# cpld.net
KiCad netlist of a schematic drawn in Altium Designer
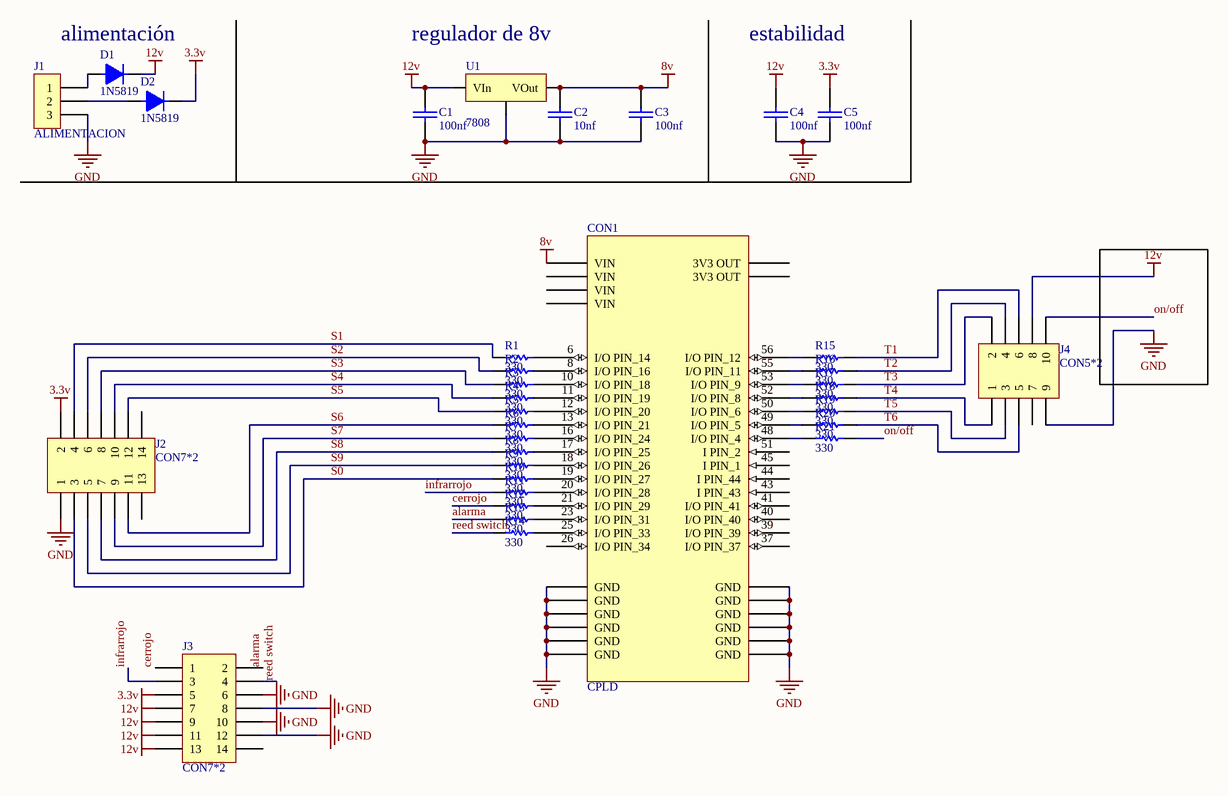
[diagram p0: cpld.SchDoc]

(export (version "E")
  (design (tool "Eeschema 10.0.6"))
  (components
    (comp (ref "C1") (value "100nf") (footprint "CAP200") (libsource (lib "LIBPIOIX") (part "CAP")))
    (comp (ref "C2") (value "10nf") (footprint "CAP200") (libsource (lib "LIBPIOIX") (part "CAP")))
    (comp (ref "C3") (value "100nf") (footprint "CAP200") (libsource (lib "LIBPIOIX") (part "CAP")))
    (comp (ref "C4") (value "100nf") (footprint "CAP200") (libsource (lib "LIBEBAL") (part "CAP")))
    (comp (ref "C5") (value "100nf") (footprint "CAP200") (libsource (lib "LIBEBAL") (part "CAP")))
    (comp (ref "CON1")
      (value "CPLD")
      (footprint "CPLD_CON")
      (description "Conector para Placa PIO CPLD")
      (fields (field (name "AUTOR") "AP"))
      (libsource (lib "CPLD_CON") (part "CPLD_CON"))
    )
    (comp (ref "D1") (value "1N5819") (footprint "DO41") (libsource (lib "LIBPIOIX") (part "DIODO")))
    (comp (ref "D2") (value "1N5819") (footprint "DO41") (libsource (lib "Libreria4") (part "DIODO")))
    (comp (ref "J1")
      (value "ALIMENTACION")
      (footprint "BORNERA3")
      (libsource (lib "Libreria4") (part "BORNERA 3"))
    )
    (comp (ref "J2") (value "CON7*2") (footprint "SIP7*2") (libsource (lib "LIBEBAL") (part "CON7*2")))
    (comp (ref "J3") (value "CON7*2") (footprint "SIP7*2") (libsource (lib "") (part "CON7*2_1")))
    (comp (ref "J4") (value "CON5*2") (footprint "SIP5*2") (libsource (lib "Libreria4") (part "CON5*2")))
    (comp (ref "R1") (value "330") (footprint "RES400") (libsource (lib "LIBPIOIX") (part "RES")))
    (comp (ref "R2") (value "330") (footprint "RES400") (libsource (lib "LIBPIOIX") (part "RES")))
    (comp (ref "R3") (value "330") (footprint "RES400") (libsource (lib "LIBPIOIX") (part "RES")))
    (comp (ref "R4") (value "330") (footprint "RES400") (libsource (lib "LIBPIOIX") (part "RES")))
    (comp (ref "R5") (value "330") (footprint "RES400") (libsource (lib "LIBPIOIX") (part "RES")))
    (comp (ref "R6") (value "330") (footprint "RES400") (libsource (lib "LIBPIOIX") (part "RES")))
    (comp (ref "R7") (value "330") (footprint "RES400") (libsource (lib "LIBPIOIX") (part "RES")))
    (comp (ref "R8") (value "330") (footprint "RES400") (libsource (lib "LIBPIOIX") (part "RES")))
    (comp (ref "R9") (value "330") (footprint "RES400") (libsource (lib "LIBPIOIX") (part "RES")))
    (comp (ref "R10") (value "330") (footprint "RES400") (libsource (lib "LIBPIOIX") (part "RES")))
    (comp (ref "R11") (value "330") (footprint "RES400") (libsource (lib "LIBPIOIX") (part "RES")))
    (comp (ref "R12") (value "330") (footprint "RES400") (libsource (lib "LIBPIOIX") (part "RES")))
    (comp (ref "R13") (value "330") (footprint "RES400") (libsource (lib "LIBPIOIX") (part "RES")))
    (comp (ref "R14") (value "330") (footprint "RES400") (libsource (lib "LIBPIOIX") (part "RES")))
    (comp (ref "R15") (value "330") (footprint "RES400") (libsource (lib "LIBPIOIX") (part "RES")))
    (comp (ref "R16") (value "330") (footprint "RES400") (libsource (lib "LIBPIOIX") (part "RES")))
    (comp (ref "R17") (value "330") (footprint "RES400") (libsource (lib "LIBPIOIX") (part "RES")))
    (comp (ref "R18") (value "330") (footprint "RES400") (libsource (lib "LIBPIOIX") (part "RES")))
    (comp (ref "R19") (value "330") (footprint "RES400") (libsource (lib "LIBPIOIX") (part "RES")))
    (comp (ref "R20") (value "330") (footprint "RES400") (libsource (lib "LIBPIOIX") (part "RES")))
    (comp (ref "R21") (value "330") (footprint "RES400") (libsource (lib "LIBPIOIX") (part "RES")))
    (comp (ref "U1")
      (value "7808")
      (footprint "TO-220 V")
      (description "REGULDOR POSITIVO")
      (libsource (lib "LIBPIOIX") (part "78XX"))
    )
  )
  (nets
    (net (code "1") (name "/S0") (class "Default")
      (node (ref "J2") (pin "3") (pinfunction "3_3") (pintype "passive"))
      (node (ref "R10") (pin "1") (pinfunction "1_1") (pintype "passive"))
    )
    (net (code "2") (name "/S1") (class "Default")
      (node (ref "J2") (pin "4") (pinfunction "4_4") (pintype "passive"))
      (node (ref "R1") (pin "1") (pinfunction "1_1") (pintype "passive"))
    )
    (net (code "3") (name "/S2") (class "Default")
      (node (ref "J2") (pin "6") (pinfunction "6_6") (pintype "passive"))
      (node (ref "R2") (pin "1") (pinfunction "1_1") (pintype "passive"))
    )
    (net (code "4") (name "/S3") (class "Default")
      (node (ref "J2") (pin "8") (pinfunction "8_8") (pintype "passive"))
      (node (ref "R3") (pin "1") (pinfunction "1_1") (pintype "passive"))
    )
    (net (code "5") (name "/S4") (class "Default")
      (node (ref "J2") (pin "10") (pinfunction "10_10") (pintype "passive"))
      (node (ref "R4") (pin "1") (pinfunction "1_1") (pintype "passive"))
    )
    (net (code "6") (name "/S5") (class "Default")
      (node (ref "J2") (pin "12") (pinfunction "12_12") (pintype "passive"))
      (node (ref "R5") (pin "1") (pinfunction "1_1") (pintype "passive"))
    )
    (net (code "7") (name "/S6") (class "Default")
      (node (ref "J2") (pin "11") (pinfunction "11_11") (pintype "passive"))
      (node (ref "R6") (pin "1") (pinfunction "1_1") (pintype "passive"))
    )
    (net (code "8") (name "/S7") (class "Default")
      (node (ref "J2") (pin "9") (pinfunction "9_9") (pintype "passive"))
      (node (ref "R7") (pin "1") (pinfunction "1_1") (pintype "passive"))
    )
    (net (code "9") (name "/S8") (class "Default")
      (node (ref "J2") (pin "7") (pinfunction "7_7") (pintype "passive"))
      (node (ref "R8") (pin "1") (pinfunction "1_1") (pintype "passive"))
    )
    (net (code "10") (name "/S9") (class "Default")
      (node (ref "J2") (pin "5") (pinfunction "5_5") (pintype "passive"))
      (node (ref "R9") (pin "1") (pinfunction "1_1") (pintype "passive"))
    )
    (net (code "11") (name "/T1") (class "Default")
      (node (ref "J4") (pin "6") (pinfunction "6_6") (pintype "passive"))
      (node (ref "R15") (pin "2") (pinfunction "2_2") (pintype "passive"))
    )
    (net (code "12") (name "/T2") (class "Default")
      (node (ref "J4") (pin "4") (pinfunction "4_4") (pintype "passive"))
      (node (ref "R16") (pin "2") (pinfunction "2_2") (pintype "passive"))
    )
    (net (code "13") (name "/T3") (class "Default")
      (node (ref "J4") (pin "2") (pinfunction "2_2") (pintype "passive"))
      (node (ref "R17") (pin "2") (pinfunction "2_2") (pintype "passive"))
    )
    (net (code "14") (name "/T4") (class "Default")
      (node (ref "J4") (pin "1") (pinfunction "1_1") (pintype "passive"))
      (node (ref "R18") (pin "2") (pinfunction "2_2") (pintype "passive"))
    )
    (net (code "15") (name "/T5") (class "Default")
      (node (ref "J4") (pin "3") (pinfunction "3_3") (pintype "passive"))
      (node (ref "R19") (pin "2") (pinfunction "2_2") (pintype "passive"))
    )
    (net (code "16") (name "/T6") (class "Default")
      (node (ref "J4") (pin "5") (pinfunction "5_5") (pintype "passive"))
      (node (ref "R20") (pin "2") (pinfunction "2_2") (pintype "passive"))
    )
    (net (code "17") (name "/alarma") (class "Default")
      (node (ref "J3") (pin "2") (pinfunction "2_2") (pintype "passive"))
      (node (ref "R13") (pin "1") (pinfunction "1_1") (pintype "passive"))
    )
    (net (code "18") (name "/cerrojo") (class "Default")
      (node (ref "J3") (pin "1") (pinfunction "1_1") (pintype "passive"))
      (node (ref "R12") (pin "1") (pinfunction "1_1") (pintype "passive"))
    )
    (net (code "19") (name "/infrarrojo") (class "Default")
      (node (ref "J3") (pin "3") (pinfunction "3_3") (pintype "passive"))
      (node (ref "R11") (pin "1") (pinfunction "1_1") (pintype "passive"))
    )
    (net (code "20") (name "/on{slash}off") (class "Default")
      (node (ref "J4") (pin "10") (pinfunction "10_10") (pintype "passive"))
      (node (ref "R21") (pin "2") (pinfunction "2_2") (pintype "passive"))
    )
    (net (code "21") (name "/reed switch") (class "Default")
      (node (ref "J3") (pin "4") (pinfunction "4_4") (pintype "passive"))
      (node (ref "R14") (pin "1") (pinfunction "1_1") (pintype "passive"))
    )
    (net (code "22") (name "3.3v") (class "Default")
      (node (ref "C5") (pin "1") (pinfunction "1_1") (pintype "passive"))
      (node (ref "D2") (pin "2") (pinfunction "2_2") (pintype "passive"))
      (node (ref "J2") (pin "2") (pinfunction "2_2") (pintype "passive"))
      (node (ref "J3") (pin "5") (pinfunction "5_5") (pintype "passive"))
    )
    (net (code "23") (name "8v") (class "Default")
      (node (ref "C2") (pin "1") (pinfunction "1_1") (pintype "passive"))
      (node (ref "C3") (pin "1") (pinfunction "1_1") (pintype "passive"))
      (node (ref "CON1") (pin "1") (pinfunction "VIN_1") (pintype "passive"))
      (node (ref "U1") (pin "3") (pinfunction "VOut_3") (pintype "passive"))
    )
    (net (code "24") (name "12v") (class "Default")
      (node (ref "C1") (pin "1") (pinfunction "1_1") (pintype "passive"))
      (node (ref "C4") (pin "1") (pinfunction "1_1") (pintype "passive"))
      (node (ref "D1") (pin "2") (pinfunction "2_2") (pintype "passive"))
      (node (ref "J3") (pin "11") (pinfunction "11_11") (pintype "passive"))
      (node (ref "J3") (pin "13") (pinfunction "13_13") (pintype "passive"))
      (node (ref "J3") (pin "7") (pinfunction "7_7") (pintype "passive"))
      (node (ref "J3") (pin "9") (pinfunction "9_9") (pintype "passive"))
      (node (ref "J4") (pin "8") (pinfunction "8_8") (pintype "passive"))
      (node (ref "U1") (pin "1") (pinfunction "VIn_1") (pintype "passive"))
    )
    (net (code "25") (name "GND") (class "Default")
      (node (ref "C1") (pin "2") (pinfunction "2_2") (pintype "passive"))
      (node (ref "C2") (pin "2") (pinfunction "2_2") (pintype "passive"))
      (node (ref "C3") (pin "2") (pinfunction "2_2") (pintype "passive"))
      (node (ref "C4") (pin "2") (pinfunction "2_2") (pintype "passive"))
      (node (ref "C5") (pin "2") (pinfunction "2_2") (pintype "passive"))
      (node (ref "CON1") (pin "2") (pinfunction "GND_2") (pintype "passive"))
      (node (ref "CON1") (pin "27") (pinfunction "GND_27") (pintype "passive"))
      (node (ref "CON1") (pin "28") (pinfunction "GND_28") (pintype "passive"))
      (node (ref "CON1") (pin "29") (pinfunction "GND_29") (pintype "passive"))
      (node (ref "CON1") (pin "3") (pinfunction "GND_3") (pintype "passive"))
      (node (ref "CON1") (pin "32") (pinfunction "GND_32") (pintype "passive"))
      (node (ref "CON1") (pin "33") (pinfunction "GND_33") (pintype "passive"))
      (node (ref "CON1") (pin "34") (pinfunction "GND_34") (pintype "passive"))
      (node (ref "CON1") (pin "4") (pinfunction "GND_4") (pintype "passive"))
      (node (ref "CON1") (pin "57") (pinfunction "GND_57") (pintype "passive"))
      (node (ref "CON1") (pin "58") (pinfunction "GND_58") (pintype "passive"))
      (node (ref "CON1") (pin "59") (pinfunction "GND_59") (pintype "passive"))
      (node (ref "J1") (pin "3") (pinfunction "3_3") (pintype "passive"))
      (node (ref "J2") (pin "1") (pinfunction "1_1") (pintype "passive"))
      (node (ref "J3") (pin "10") (pinfunction "10_10") (pintype "passive"))
      (node (ref "J3") (pin "12") (pinfunction "12_12") (pintype "passive"))
      (node (ref "J3") (pin "6") (pinfunction "6_6") (pintype "passive"))
      (node (ref "J3") (pin "8") (pinfunction "8_8") (pintype "passive"))
      (node (ref "J4") (pin "9") (pinfunction "9_9") (pintype "passive"))
      (node (ref "U1") (pin "2") (pinfunction "GND_2") (pintype "passive"))
    )
    (net (code "26") (name "Net-(CON1-I{slash}O_PIN_4)") (class "Default")
      (node (ref "CON1") (pin "48") (pinfunction "I/O_PIN_4_48") (pintype "bidirectional"))
      (node (ref "R21") (pin "1") (pinfunction "1_1") (pintype "passive"))
    )
    (net (code "27") (name "Net-(CON1-I{slash}O_PIN_5)") (class "Default")
      (node (ref "CON1") (pin "49") (pinfunction "I/O_PIN_5_49") (pintype "bidirectional"))
      (node (ref "R20") (pin "1") (pinfunction "1_1") (pintype "passive"))
    )
    (net (code "28") (name "Net-(CON1-I{slash}O_PIN_6)") (class "Default")
      (node (ref "CON1") (pin "50") (pinfunction "I/O_PIN_6_50") (pintype "bidirectional"))
      (node (ref "R19") (pin "1") (pinfunction "1_1") (pintype "passive"))
    )
    (net (code "29") (name "Net-(CON1-I{slash}O_PIN_8)") (class "Default")
      (node (ref "CON1") (pin "52") (pinfunction "I/O_PIN_8_52") (pintype "bidirectional"))
      (node (ref "R18") (pin "1") (pinfunction "1_1") (pintype "passive"))
    )
    (net (code "30") (name "Net-(CON1-I{slash}O_PIN_9)") (class "Default")
      (node (ref "CON1") (pin "53") (pinfunction "I/O_PIN_9_53") (pintype "bidirectional"))
      (node (ref "R17") (pin "1") (pinfunction "1_1") (pintype "passive"))
    )
    (net (code "31") (name "Net-(CON1-I{slash}O_PIN_11)") (class "Default")
      (node (ref "CON1") (pin "55") (pinfunction "I/O_PIN_11_55") (pintype "bidirectional"))
      (node (ref "R16") (pin "1") (pinfunction "1_1") (pintype "passive"))
    )
    (net (code "32") (name "Net-(CON1-I{slash}O_PIN_12)") (class "Default")
      (node (ref "CON1") (pin "56") (pinfunction "I/O_PIN_12_56") (pintype "bidirectional"))
      (node (ref "R15") (pin "1") (pinfunction "1_1") (pintype "passive"))
    )
    (net (code "33") (name "Net-(CON1-I{slash}O_PIN_14)") (class "Default")
      (node (ref "CON1") (pin "6") (pinfunction "I/O_PIN_14_6") (pintype "bidirectional"))
      (node (ref "R1") (pin "2") (pinfunction "2_2") (pintype "passive"))
    )
    (net (code "34") (name "Net-(CON1-I{slash}O_PIN_16)") (class "Default")
      (node (ref "CON1") (pin "8") (pinfunction "I/O_PIN_16_8") (pintype "bidirectional"))
      (node (ref "R2") (pin "2") (pinfunction "2_2") (pintype "passive"))
    )
    (net (code "35") (name "Net-(CON1-I{slash}O_PIN_18)") (class "Default")
      (node (ref "CON1") (pin "10") (pinfunction "I/O_PIN_18_10") (pintype "bidirectional"))
      (node (ref "R3") (pin "2") (pinfunction "2_2") (pintype "passive"))
    )
    (net (code "36") (name "Net-(CON1-I{slash}O_PIN_19)") (class "Default")
      (node (ref "CON1") (pin "11") (pinfunction "I/O_PIN_19_11") (pintype "bidirectional"))
      (node (ref "R4") (pin "2") (pinfunction "2_2") (pintype "passive"))
    )
    (net (code "37") (name "Net-(CON1-I{slash}O_PIN_20)") (class "Default")
      (node (ref "CON1") (pin "12") (pinfunction "I/O_PIN_20_12") (pintype "bidirectional"))
      (node (ref "R5") (pin "2") (pinfunction "2_2") (pintype "passive"))
    )
    (net (code "38") (name "Net-(CON1-I{slash}O_PIN_21)") (class "Default")
      (node (ref "CON1") (pin "13") (pinfunction "I/O_PIN_21_13") (pintype "bidirectional"))
      (node (ref "R6") (pin "2") (pinfunction "2_2") (pintype "passive"))
    )
    (net (code "39") (name "Net-(CON1-I{slash}O_PIN_24)") (class "Default")
      (node (ref "CON1") (pin "16") (pinfunction "I/O_PIN_24_16") (pintype "bidirectional"))
      (node (ref "R7") (pin "2") (pinfunction "2_2") (pintype "passive"))
    )
    (net (code "40") (name "Net-(CON1-I{slash}O_PIN_25)") (class "Default")
      (node (ref "CON1") (pin "17") (pinfunction "I/O_PIN_25_17") (pintype "bidirectional"))
      (node (ref "R8") (pin "2") (pinfunction "2_2") (pintype "passive"))
    )
    (net (code "41") (name "Net-(CON1-I{slash}O_PIN_26)") (class "Default")
      (node (ref "CON1") (pin "18") (pinfunction "I/O_PIN_26_18") (pintype "bidirectional"))
      (node (ref "R9") (pin "2") (pinfunction "2_2") (pintype "passive"))
    )
    (net (code "42") (name "Net-(CON1-I{slash}O_PIN_27)") (class "Default")
      (node (ref "CON1") (pin "19") (pinfunction "I/O_PIN_27_19") (pintype "bidirectional"))
      (node (ref "R10") (pin "2") (pinfunction "2_2") (pintype "passive"))
    )
    (net (code "43") (name "Net-(CON1-I{slash}O_PIN_28)") (class "Default")
      (node (ref "CON1") (pin "20") (pinfunction "I/O_PIN_28_20") (pintype "bidirectional"))
      (node (ref "R11") (pin "2") (pinfunction "2_2") (pintype "passive"))
    )
    (net (code "44") (name "Net-(CON1-I{slash}O_PIN_29)") (class "Default")
      (node (ref "CON1") (pin "21") (pinfunction "I/O_PIN_29_21") (pintype "bidirectional"))
      (node (ref "R12") (pin "2") (pinfunction "2_2") (pintype "passive"))
    )
    (net (code "45") (name "Net-(CON1-I{slash}O_PIN_31)") (class "Default")
      (node (ref "CON1") (pin "23") (pinfunction "I/O_PIN_31_23") (pintype "bidirectional"))
      (node (ref "R13") (pin "2") (pinfunction "2_2") (pintype "passive"))
    )
    (net (code "46") (name "Net-(CON1-I{slash}O_PIN_33)") (class "Default")
      (node (ref "CON1") (pin "25") (pinfunction "I/O_PIN_33_25") (pintype "bidirectional"))
      (node (ref "R14") (pin "2") (pinfunction "2_2") (pintype "passive"))
    )
    (net (code "47") (name "Net-(D1-Pad1)") (class "Default")
      (node (ref "D1") (pin "1") (pinfunction "1_1") (pintype "passive"))
      (node (ref "J1") (pin "1") (pinfunction "1_1") (pintype "passive"))
    )
    (net (code "48") (name "Net-(D2-Pad1)") (class "Default")
      (node (ref "D2") (pin "1") (pinfunction "1_1") (pintype "passive"))
      (node (ref "J1") (pin "2") (pinfunction "2_2") (pintype "passive"))
    )
    (net (code "49") (name "unconnected-(CON1-3V3_OUT-Pad14)") (class "Default")
      (node (ref "CON1") (pin "14") (pinfunction "3V3_OUT_14") (pintype "passive"))
    )
    (net (code "50") (name "unconnected-(CON1-3V3_OUT-Pad15)") (class "Default")
      (node (ref "CON1") (pin "15") (pinfunction "3V3_OUT_15") (pintype "passive"))
    )
    (net (code "51") (name "unconnected-(CON1-I_PIN_1-Pad45)") (class "Default")
      (node (ref "CON1") (pin "45") (pinfunction "I_PIN_1_45") (pintype "input"))
    )
    (net (code "52") (name "unconnected-(CON1-I_PIN_2-Pad51)") (class "Default")
      (node (ref "CON1") (pin "51") (pinfunction "I_PIN_2_51") (pintype "input"))
    )
    (net (code "53") (name "unconnected-(CON1-I_PIN_43-Pad43)") (class "Default")
      (node (ref "CON1") (pin "43") (pinfunction "I_PIN_43_43") (pintype "input"))
    )
    (net (code "54") (name "unconnected-(CON1-I_PIN_44-Pad44)") (class "Default")
      (node (ref "CON1") (pin "44") (pinfunction "I_PIN_44_44") (pintype "input"))
    )
    (net (code "55") (name "unconnected-(CON1-I{slash}O_PIN_34-Pad26)") (class "Default")
      (node (ref "CON1") (pin "26") (pinfunction "I/O_PIN_34_26") (pintype "bidirectional"))
    )
    (net (code "56") (name "unconnected-(CON1-I{slash}O_PIN_37-Pad37)") (class "Default")
      (node (ref "CON1") (pin "37") (pinfunction "I/O_PIN_37_37") (pintype "bidirectional"))
    )
    (net (code "57") (name "unconnected-(CON1-I{slash}O_PIN_39-Pad39)") (class "Default")
      (node (ref "CON1") (pin "39") (pinfunction "I/O_PIN_39_39") (pintype "bidirectional"))
    )
    (net (code "58") (name "unconnected-(CON1-I{slash}O_PIN_40-Pad40)") (class "Default")
      (node (ref "CON1") (pin "40") (pinfunction "I/O_PIN_40_40") (pintype "bidirectional"))
    )
    (net (code "59") (name "unconnected-(CON1-I{slash}O_PIN_41-Pad41)") (class "Default")
      (node (ref "CON1") (pin "41") (pinfunction "I/O_PIN_41_41") (pintype "bidirectional"))
    )
    (net (code "60") (name "unconnected-(CON1-VIN-Pad30)") (class "Default")
      (node (ref "CON1") (pin "30") (pinfunction "VIN_30") (pintype "passive"))
    )
    (net (code "61") (name "unconnected-(CON1-VIN-Pad31)") (class "Default")
      (node (ref "CON1") (pin "31") (pinfunction "VIN_31") (pintype "passive"))
    )
    (net (code "62") (name "unconnected-(CON1-VIN-Pad60)") (class "Default")
      (node (ref "CON1") (pin "60") (pinfunction "VIN_60") (pintype "passive"))
    )
    (net (code "63") (name "unconnected-(J2-Pad13)") (class "Default")
      (node (ref "J2") (pin "13") (pinfunction "13_13") (pintype "passive"))
    )
    (net (code "64") (name "unconnected-(J2-Pad14)") (class "Default")
      (node (ref "J2") (pin "14") (pinfunction "14_14") (pintype "passive"))
    )
    (net (code "65") (name "unconnected-(J3-Pad14)") (class "Default")
      (node (ref "J3") (pin "14") (pinfunction "14_14") (pintype "passive"))
    )
    (net (code "66") (name "unconnected-(J4-Pad7)") (class "Default")
      (node (ref "J4") (pin "7") (pinfunction "7_7") (pintype "passive"))
    )
  )
)
